# CPU.net
KiCad netlist of a schematic drawn in Altium Designer
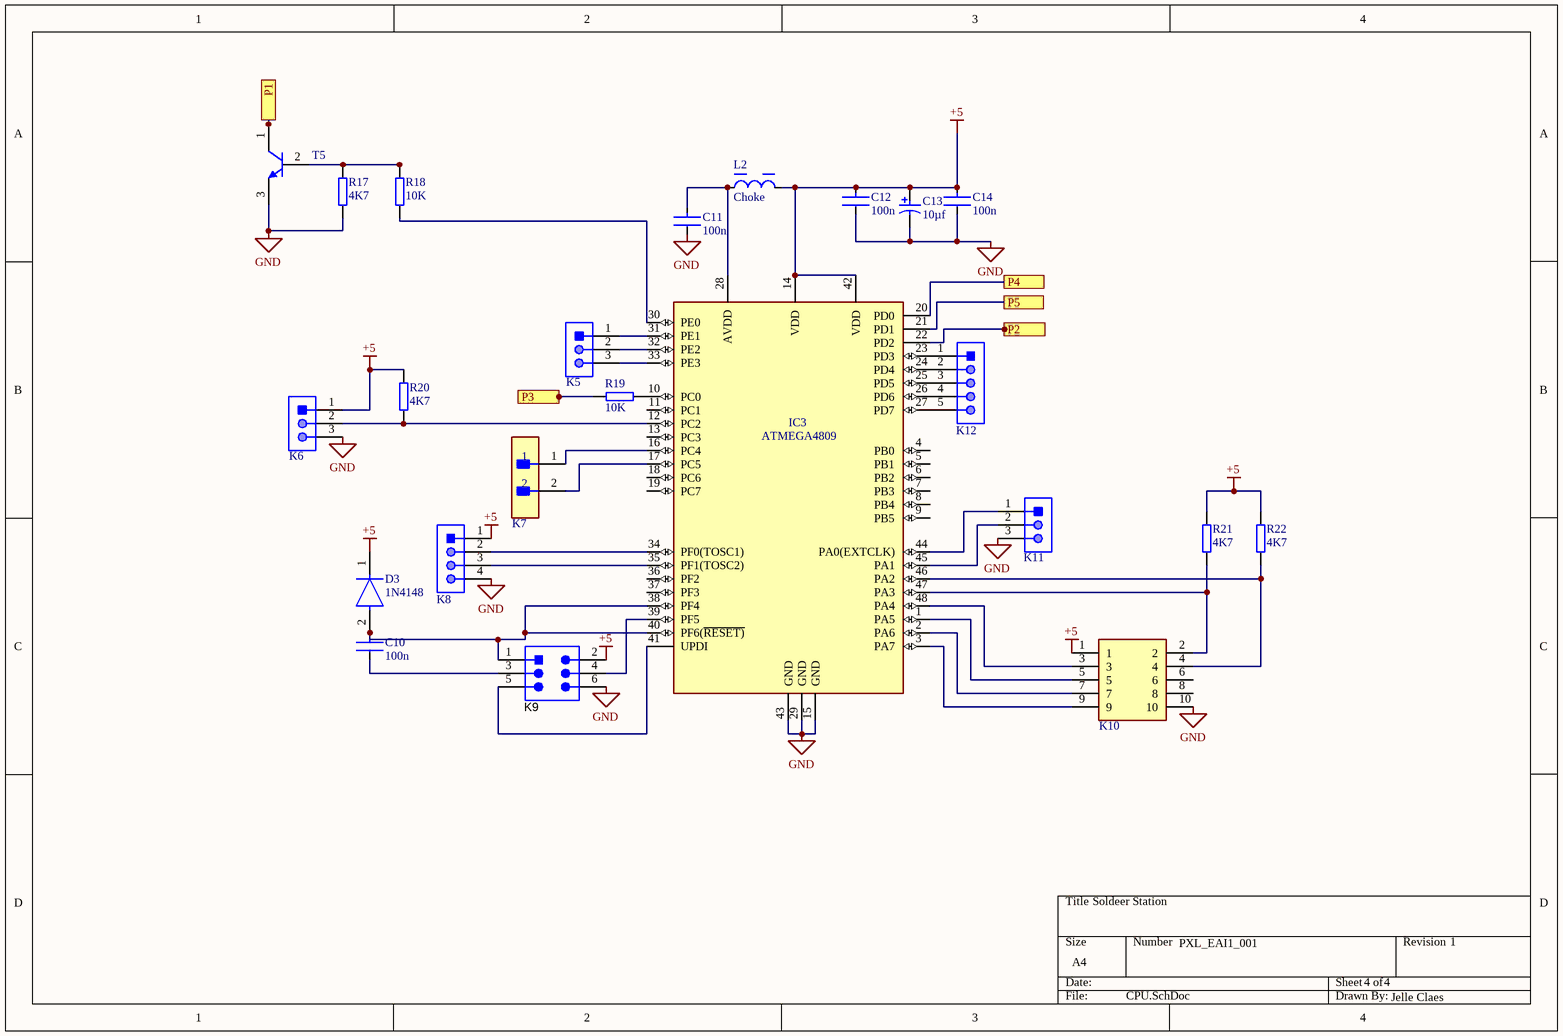
[diagram p0: CPU.SchDoc]

(export (version "E")
  (design (tool "Eeschema 10.0.6"))
  (components
    (comp (ref "C10")
      (value "100n")
      (footprint "CC_0805_m")
      (fields
        (field (name "MANUFACTURER") "KEMET")
        (field (name "OCTOPART") "https://octopart.com/c0805c224k5ractu-kemet-144670")
        (field (name "MANUFACTURER PART NUMBER") "C0805C224K5RACTU")
      )
      (libsource (lib "soldeerstation") (part "Capacitor_Ceramic"))
    )
    (comp (ref "C11")
      (value "100n")
      (footprint "CC_0805_m")
      (fields
        (field (name "MANUFACTURER") "KEMET")
        (field (name "OCTOPART") "https://octopart.com/c0805c224k5ractu-kemet-144670")
        (field (name "MANUFACTURER PART NUMBER") "C0805C224K5RACTU")
      )
      (libsource (lib "soldeerstation") (part "Capacitor_Ceramic"))
    )
    (comp (ref "C12")
      (value "100n")
      (footprint "CC_0805_L")
      (fields
        (field (name "MANUFACTURER") "KEMET")
        (field (name "OCTOPART") "https://octopart.com/c0805c224k5ractu-kemet-144670")
        (field (name "MANUFACTURER PART NUMBER") "C0805C224K5RACTU")
      )
      (libsource (lib "soldeerstation") (part "Capacitor_Ceramic"))
    )
    (comp (ref "C13")
      (value "10µf")
      (footprint "D4L5.4")
      (fields (field (name "MANUFACTURER") "Panasonic"))
      (libsource (lib "soldeerstation") (part "Capacitor_Electrolytic"))
    )
    (comp (ref "C14")
      (value "100n")
      (footprint "CC_0805_L")
      (fields
        (field (name "MANUFACTURER") "KEMET")
        (field (name "OCTOPART") "https://octopart.com/c0805c224k5ractu-kemet-144670")
        (field (name "MANUFACTURER PART NUMBER") "C0805C224K5RACTU")
      )
      (libsource (lib "soldeerstation") (part "Capacitor_Ceramic"))
    )
    (comp (ref "D3")
      (value "1N4148")
      (footprint "SOD-123FL")
      (fields
        (field (name "MANUFACTURER PART NUMBER") "1N4007")
        (field (name "MANUFACTURER") "Diotec")
        (field (name "OCTOPART") "https://octopart.com/1n4007-diotec-4040411")
      )
      (libsource (lib "soldeerstation") (part "Diode"))
    )
    (comp (ref "IC3")
      (value "ATMEGA4809")
      (footprint "TQFP_48_M")
      (libsource (lib "soldeerstation") (part "ATMEGA4809"))
    )
    (comp (ref "K5")
      (value "22-28-4033")
      (footprint "MOLX-22-28-4033_V")
      (description "Male Header, Pitch 2.54 mm, 1 x 3 Position, Height 8.38 mm, Tail Length 3.18 mm, RoHS, Bulk")
      (fields (field (name "MANUFACTURER") "Molex"))
      (libsource (lib "") (part "CMP-1676-00001-5_1"))
    )
    (comp (ref "K6")
      (value "22-28-4033")
      (footprint "MOLX-22-28-4033_V")
      (description "Male Header, Pitch 2.54 mm, 1 x 3 Position, Height 8.38 mm, Tail Length 3.18 mm, RoHS, Bulk")
      (fields (field (name "MANUFACTURER") "Molex"))
      (libsource (lib "") (part "CMP-1676-00001-5_1"))
    )
    (comp (ref "K7")
      (value "M22-2510205")
      (footprint "FP-M22-2510205-MFG")
      (description "CONN HEADER VERT 2POS 2MM")
      (fields
        (field (name "MANUFACTURER") "Harwin")
        (field (name "OCTOPART") "https://octopart.com/m22-2510205-harwin-2538221")
      )
      (libsource (lib "soldeerstation") (part "CMP-15831-000005-1"))
    )
    (comp (ref "K8")
      (value "61300411121")
      (footprint "61300411121")
      (description "THT Vertical Pin Header WR-PHD, Pitch 2.54 mm, Single Row, 4 pins")
      (fields (field (name "MANUFACTURER") "Wurth Elektronik") (field (name "PUBLISHER") "WurthElektronik"))
      (libsource (lib "soldeerstation") (part "CMP-1502-01064-1"))
    )
    (comp (ref "K9")
      (value "TSW-103-07-G-D")
      (footprint "SMTC-TSW-103-07-G-D_V")
      (fields (field (name "MANUFACTURER") "Samtec-Inc."))
      (libsource (lib "soldeerstation") (part "CMP-2000-07329-1"))
    )
    (comp (ref "K10")
      (value "5x2 box pinheader")
      (footprint "2x5 box pinheader")
      (description "Connector")
      (fields (field (name "MANUFACTURER_PART_NUMBER") "T821110A1S100CEU"))
      (libsource (lib "soldeerstation") (part "5x2 box pinheader"))
    )
    (comp (ref "K11")
      (value "22-28-4033")
      (footprint "MOLX-22-28-4033_V")
      (description "Male Header, Pitch 2.54 mm, 1 x 3 Position, Height 8.38 mm, Tail Length 3.18 mm, RoHS, Bulk")
      (fields (field (name "MANUFACTURER") "Molex"))
      (libsource (lib "soldeerstation") (part "CMP-1676-00001-5"))
    )
    (comp (ref "K12")
      (value "61300511121")
      (footprint "61300511121")
      (description "THT Vertical Pin Header WR-PHD, Pitch 2.54 mm, Single Row, 5 pins")
      (fields (field (name "MANUFACTURER") "Wurth Elektronik") (field (name "PUBLISHER") "WurthElektronik"))
      (libsource (lib "soldeerstation") (part "5pin"))
    )
    (comp (ref "L2")
      (value "Choke")
      (footprint "CC_0805_L")
      (fields (field (name "TOLERANCE") "20%"))
      (libsource (lib "soldeerstation") (part "Choke"))
    )
    (comp (ref "R17")
      (value "4K7")
      (footprint "R_0805_M")
      (fields (field (name "MANUFACTURER") "Vishay Dale") (field (name "PART NUMBER") "CRCW08050000Z0EA"))
      (libsource (lib "soldeerstation") (part "Resistor"))
    )
    (comp (ref "R18")
      (value "10K")
      (footprint "R_0805_M")
      (fields (field (name "MANUFACTURER") "Vishay Dale") (field (name "PART NUMBER") "CRCW08050000Z0EA"))
      (libsource (lib "soldeerstation") (part "Resistor"))
    )
    (comp (ref "R19")
      (value "10K")
      (footprint "R_0805_M")
      (fields (field (name "MANUFACTURER") "Vishay Dale") (field (name "PART NUMBER") "CRCW08050000Z0EA"))
      (libsource (lib "soldeerstation") (part "Resistor"))
    )
    (comp (ref "R20")
      (value "4K7")
      (footprint "R_0805_M")
      (fields (field (name "MANUFACTURER") "Vishay Dale") (field (name "PART NUMBER") "CRCW08050000Z0EA"))
      (libsource (lib "soldeerstation") (part "Resistor"))
    )
    (comp (ref "R21")
      (value "4K7")
      (footprint "R_0805_M")
      (fields (field (name "MANUFACTURER") "Vishay Dale") (field (name "PART NUMBER") "CRCW08050000Z0EA"))
      (libsource (lib "soldeerstation") (part "Resistor"))
    )
    (comp (ref "R22")
      (value "4K7")
      (footprint "R_0805_M")
      (fields (field (name "MANUFACTURER") "Vishay Dale") (field (name "PART NUMBER") "CRCW08050000Z0EA"))
      (libsource (lib "soldeerstation") (part "Resistor"))
    )
    (comp (ref "T5")
      (value "Transistor_NPN")
      (footprint "SOT_23")
      (fields (field (name "MANUFACTURER") "On Semiconductor") (field (name "PARTNUMBER") "BC547C"))
      (libsource (lib "soldeerstation") (part "Transistor_NPN"))
    )
  )
  (nets
    (net (code "1") (name "+5") (class "Default")
      (node (ref "C12") (pin "1") (pinfunction "1_1") (pintype "passive"))
      (node (ref "C13") (pin "2") (pinfunction "2_2") (pintype "passive"))
      (node (ref "C14") (pin "1") (pinfunction "1_1") (pintype "passive"))
      (node (ref "D3") (pin "1") (pinfunction "C_1") (pintype "passive"))
      (node (ref "IC3") (pin "14") (pinfunction "VDD_14") (pintype "power_in"))
      (node (ref "IC3") (pin "42") (pinfunction "VDD_42") (pintype "power_in"))
      (node (ref "K10") (pin "1") (pinfunction "1_1") (pintype "passive"))
      (node (ref "K6") (pin "1") (pinfunction "1_1") (pintype "passive"))
      (node (ref "K8") (pin "1") (pinfunction "1_1") (pintype "passive"))
      (node (ref "K9") (pin "2") (pinfunction "2_2") (pintype "passive"))
      (node (ref "L2") (pin "2") (pinfunction "2_2") (pintype "passive"))
      (node (ref "R20") (pin "2") (pinfunction "2_2") (pintype "passive"))
      (node (ref "R21") (pin "2") (pinfunction "2_2") (pintype "passive"))
      (node (ref "R22") (pin "2") (pinfunction "2_2") (pintype "passive"))
    )
    (net (code "2") (name "/P1") (class "Default")
      (node (ref "T5") (pin "1") (pinfunction "C_1") (pintype "passive"))
    )
    (net (code "3") (name "/P2") (class "Default")
      (node (ref "IC3") (pin "22") (pinfunction "PD2_22") (pintype "passive"))
    )
    (net (code "4") (name "/P3") (class "Default")
      (node (ref "R19") (pin "1") (pinfunction "1_1") (pintype "passive"))
    )
    (net (code "5") (name "/P4") (class "Default")
      (node (ref "IC3") (pin "20") (pinfunction "PD0_20") (pintype "passive"))
    )
    (net (code "6") (name "/P5") (class "Default")
      (node (ref "IC3") (pin "21") (pinfunction "PD1_21") (pintype "passive"))
    )
    (net (code "7") (name "GND") (class "Default")
      (node (ref "C11") (pin "2") (pinfunction "2_2") (pintype "passive"))
      (node (ref "C12") (pin "2") (pinfunction "2_2") (pintype "passive"))
      (node (ref "C13") (pin "1") (pinfunction "1_1") (pintype "passive"))
      (node (ref "C14") (pin "2") (pinfunction "2_2") (pintype "passive"))
      (node (ref "IC3") (pin "15") (pinfunction "GND_15") (pintype "passive"))
      (node (ref "IC3") (pin "29") (pinfunction "GND_29") (pintype "passive"))
      (node (ref "IC3") (pin "43") (pinfunction "GND_43") (pintype "passive"))
      (node (ref "K10") (pin "10") (pinfunction "10_10") (pintype "passive"))
      (node (ref "K11") (pin "3") (pinfunction "3_3") (pintype "passive"))
      (node (ref "K6") (pin "3") (pinfunction "3_3") (pintype "passive"))
      (node (ref "K8") (pin "4") (pinfunction "4_4") (pintype "passive"))
      (node (ref "K9") (pin "6") (pinfunction "6_6") (pintype "passive"))
      (node (ref "R17") (pin "1") (pinfunction "1_1") (pintype "passive"))
      (node (ref "T5") (pin "3") (pinfunction "E_3") (pintype "passive"))
    )
    (net (code "8") (name "Net-(C10-Pad2)") (class "Default")
      (node (ref "C10") (pin "2") (pinfunction "2_2") (pintype "passive"))
      (node (ref "K9") (pin "3") (pinfunction "3_3") (pintype "passive"))
    )
    (net (code "9") (name "Net-(D3-A)") (class "Default")
      (node (ref "C10") (pin "1") (pinfunction "1_1") (pintype "passive"))
      (node (ref "D3") (pin "2") (pinfunction "A_2") (pintype "passive"))
      (node (ref "IC3") (pin "38") (pinfunction "PF4_38") (pintype "bidirectional"))
      (node (ref "IC3") (pin "40") (pinfunction "PF6(~{RESET)}_40") (pintype "bidirectional"))
      (node (ref "K9") (pin "1") (pinfunction "1_1") (pintype "passive"))
    )
    (net (code "10") (name "Net-(IC3-AVDD)") (class "Default")
      (node (ref "C11") (pin "1") (pinfunction "1_1") (pintype "passive"))
      (node (ref "IC3") (pin "28") (pinfunction "AVDD_28") (pintype "power_in"))
      (node (ref "L2") (pin "1") (pinfunction "1_1") (pintype "passive"))
    )
    (net (code "11") (name "Net-(IC3-PA0(EXTCLK))") (class "Default")
      (node (ref "IC3") (pin "44") (pinfunction "PA0(EXTCLK)_44") (pintype "bidirectional"))
      (node (ref "K11") (pin "1") (pinfunction "1_1") (pintype "passive"))
    )
    (net (code "12") (name "Net-(IC3-PA1)") (class "Default")
      (node (ref "IC3") (pin "45") (pinfunction "PA1_45") (pintype "bidirectional"))
      (node (ref "K11") (pin "2") (pinfunction "2_2") (pintype "passive"))
    )
    (net (code "13") (name "Net-(IC3-PA2)") (class "Default")
      (node (ref "IC3") (pin "46") (pinfunction "PA2_46") (pintype "bidirectional"))
      (node (ref "K10") (pin "4") (pinfunction "4_4") (pintype "passive"))
      (node (ref "R22") (pin "1") (pinfunction "1_1") (pintype "passive"))
    )
    (net (code "14") (name "Net-(IC3-PA3)") (class "Default")
      (node (ref "IC3") (pin "47") (pinfunction "PA3_47") (pintype "bidirectional"))
      (node (ref "K10") (pin "2") (pinfunction "2_2") (pintype "passive"))
      (node (ref "R21") (pin "1") (pinfunction "1_1") (pintype "passive"))
    )
    (net (code "15") (name "Net-(IC3-PA4)") (class "Default")
      (node (ref "IC3") (pin "48") (pinfunction "PA4_48") (pintype "bidirectional"))
      (node (ref "K10") (pin "3") (pinfunction "3_3") (pintype "passive"))
    )
    (net (code "16") (name "Net-(IC3-PA5)") (class "Default")
      (node (ref "IC3") (pin "1") (pinfunction "PA5_1") (pintype "bidirectional"))
      (node (ref "K10") (pin "5") (pinfunction "5_5") (pintype "passive"))
    )
    (net (code "17") (name "Net-(IC3-PA6)") (class "Default")
      (node (ref "IC3") (pin "2") (pinfunction "PA6_2") (pintype "bidirectional"))
      (node (ref "K10") (pin "7") (pinfunction "7_7") (pintype "passive"))
    )
    (net (code "18") (name "Net-(IC3-PA7)") (class "Default")
      (node (ref "IC3") (pin "3") (pinfunction "PA7_3") (pintype "bidirectional"))
      (node (ref "K10") (pin "9") (pinfunction "9_9") (pintype "passive"))
    )
    (net (code "19") (name "Net-(IC3-PC0)") (class "Default")
      (node (ref "IC3") (pin "10") (pinfunction "PC0_10") (pintype "bidirectional"))
      (node (ref "R19") (pin "2") (pinfunction "2_2") (pintype "passive"))
    )
    (net (code "20") (name "Net-(IC3-PC2)") (class "Default")
      (node (ref "IC3") (pin "12") (pinfunction "PC2_12") (pintype "bidirectional"))
      (node (ref "K6") (pin "2") (pinfunction "2_2") (pintype "passive"))
      (node (ref "R20") (pin "1") (pinfunction "1_1") (pintype "passive"))
    )
    (net (code "21") (name "Net-(IC3-PC4)") (class "Default")
      (node (ref "IC3") (pin "16") (pinfunction "PC4_16") (pintype "bidirectional"))
      (node (ref "K7") (pin "1") (pinfunction "1_1") (pintype "passive"))
    )
    (net (code "22") (name "Net-(IC3-PC5)") (class "Default")
      (node (ref "IC3") (pin "17") (pinfunction "PC5_17") (pintype "bidirectional"))
      (node (ref "K7") (pin "2") (pinfunction "2_2") (pintype "passive"))
    )
    (net (code "23") (name "Net-(IC3-PD3)") (class "Default")
      (node (ref "IC3") (pin "23") (pinfunction "PD3_23") (pintype "bidirectional"))
      (node (ref "K12") (pin "1") (pinfunction "1_1") (pintype "passive"))
    )
    (net (code "24") (name "Net-(IC3-PD4)") (class "Default")
      (node (ref "IC3") (pin "24") (pinfunction "PD4_24") (pintype "bidirectional"))
      (node (ref "K12") (pin "2") (pinfunction "2_2") (pintype "passive"))
    )
    (net (code "25") (name "Net-(IC3-PD5)") (class "Default")
      (node (ref "IC3") (pin "25") (pinfunction "PD5_25") (pintype "bidirectional"))
      (node (ref "K12") (pin "3") (pinfunction "3_3") (pintype "passive"))
    )
    (net (code "26") (name "Net-(IC3-PD6)") (class "Default")
      (node (ref "IC3") (pin "26") (pinfunction "PD6_26") (pintype "bidirectional"))
      (node (ref "K12") (pin "4") (pinfunction "4_4") (pintype "passive"))
    )
    (net (code "27") (name "Net-(IC3-PD7)") (class "Default")
      (node (ref "IC3") (pin "27") (pinfunction "PD7_27") (pintype "bidirectional"))
      (node (ref "K12") (pin "5") (pinfunction "5_5") (pintype "passive"))
    )
    (net (code "28") (name "Net-(IC3-PE0)") (class "Default")
      (node (ref "IC3") (pin "30") (pinfunction "PE0_30") (pintype "bidirectional"))
      (node (ref "R18") (pin "1") (pinfunction "1_1") (pintype "passive"))
    )
    (net (code "29") (name "Net-(IC3-PE1)") (class "Default")
      (node (ref "IC3") (pin "31") (pinfunction "PE1_31") (pintype "bidirectional"))
      (node (ref "K5") (pin "1") (pinfunction "1_1") (pintype "passive"))
    )
    (net (code "30") (name "Net-(IC3-PE2)") (class "Default")
      (node (ref "IC3") (pin "32") (pinfunction "PE2_32") (pintype "bidirectional"))
      (node (ref "K5") (pin "2") (pinfunction "2_2") (pintype "passive"))
    )
    (net (code "31") (name "Net-(IC3-PE3)") (class "Default")
      (node (ref "IC3") (pin "33") (pinfunction "PE3_33") (pintype "bidirectional"))
      (node (ref "K5") (pin "3") (pinfunction "3_3") (pintype "passive"))
    )
    (net (code "32") (name "Net-(IC3-PF0(TOSC1))") (class "Default")
      (node (ref "IC3") (pin "34") (pinfunction "PF0(TOSC1)_34") (pintype "bidirectional"))
      (node (ref "K8") (pin "2") (pinfunction "2_2") (pintype "passive"))
    )
    (net (code "33") (name "Net-(IC3-PF1(TOSC2))") (class "Default")
      (node (ref "IC3") (pin "35") (pinfunction "PF1(TOSC2)_35") (pintype "bidirectional"))
      (node (ref "K8") (pin "3") (pinfunction "3_3") (pintype "passive"))
    )
    (net (code "34") (name "Net-(IC3-PF5)") (class "Default")
      (node (ref "IC3") (pin "39") (pinfunction "PF5_39") (pintype "bidirectional"))
      (node (ref "K9") (pin "4") (pinfunction "4_4") (pintype "passive"))
    )
    (net (code "35") (name "Net-(IC3-UPDI)") (class "Default")
      (node (ref "IC3") (pin "41") (pinfunction "UPDI_41") (pintype "passive"))
      (node (ref "K9") (pin "5") (pinfunction "5_5") (pintype "passive"))
    )
    (net (code "36") (name "Net-(T5-B)") (class "Default")
      (node (ref "R17") (pin "2") (pinfunction "2_2") (pintype "passive"))
      (node (ref "R18") (pin "2") (pinfunction "2_2") (pintype "passive"))
      (node (ref "T5") (pin "2") (pinfunction "B_2") (pintype "passive"))
    )
    (net (code "37") (name "unconnected-(IC3-PB0-Pad4)") (class "Default")
      (node (ref "IC3") (pin "4") (pinfunction "PB0_4") (pintype "bidirectional"))
    )
    (net (code "38") (name "unconnected-(IC3-PB1-Pad5)") (class "Default")
      (node (ref "IC3") (pin "5") (pinfunction "PB1_5") (pintype "bidirectional"))
    )
    (net (code "39") (name "unconnected-(IC3-PB2-Pad6)") (class "Default")
      (node (ref "IC3") (pin "6") (pinfunction "PB2_6") (pintype "bidirectional"))
    )
    (net (code "40") (name "unconnected-(IC3-PB3-Pad7)") (class "Default")
      (node (ref "IC3") (pin "7") (pinfunction "PB3_7") (pintype "bidirectional"))
    )
    (net (code "41") (name "unconnected-(IC3-PB4-Pad8)") (class "Default")
      (node (ref "IC3") (pin "8") (pinfunction "PB4_8") (pintype "bidirectional"))
    )
    (net (code "42") (name "unconnected-(IC3-PB5-Pad9)") (class "Default")
      (node (ref "IC3") (pin "9") (pinfunction "PB5_9") (pintype "bidirectional"))
    )
    (net (code "43") (name "unconnected-(IC3-PC1-Pad11)") (class "Default")
      (node (ref "IC3") (pin "11") (pinfunction "PC1_11") (pintype "bidirectional"))
    )
    (net (code "44") (name "unconnected-(IC3-PC3-Pad13)") (class "Default")
      (node (ref "IC3") (pin "13") (pinfunction "PC3_13") (pintype "bidirectional"))
    )
    (net (code "45") (name "unconnected-(IC3-PC6-Pad18)") (class "Default")
      (node (ref "IC3") (pin "18") (pinfunction "PC6_18") (pintype "bidirectional"))
    )
    (net (code "46") (name "unconnected-(IC3-PC7-Pad19)") (class "Default")
      (node (ref "IC3") (pin "19") (pinfunction "PC7_19") (pintype "bidirectional"))
    )
    (net (code "47") (name "unconnected-(IC3-PF2-Pad36)") (class "Default")
      (node (ref "IC3") (pin "36") (pinfunction "PF2_36") (pintype "bidirectional"))
    )
    (net (code "48") (name "unconnected-(IC3-PF3-Pad37)") (class "Default")
      (node (ref "IC3") (pin "37") (pinfunction "PF3_37") (pintype "bidirectional"))
    )
    (net (code "49") (name "unconnected-(K10-Pad6)") (class "Default")
      (node (ref "K10") (pin "6") (pinfunction "6_6") (pintype "passive"))
    )
    (net (code "50") (name "unconnected-(K10-Pad8)") (class "Default")
      (node (ref "K10") (pin "8") (pinfunction "8_8") (pintype "passive"))
    )
  )
)
